# AnalogIO.net
KiCad netlist of a schematic drawn in Altium Designer
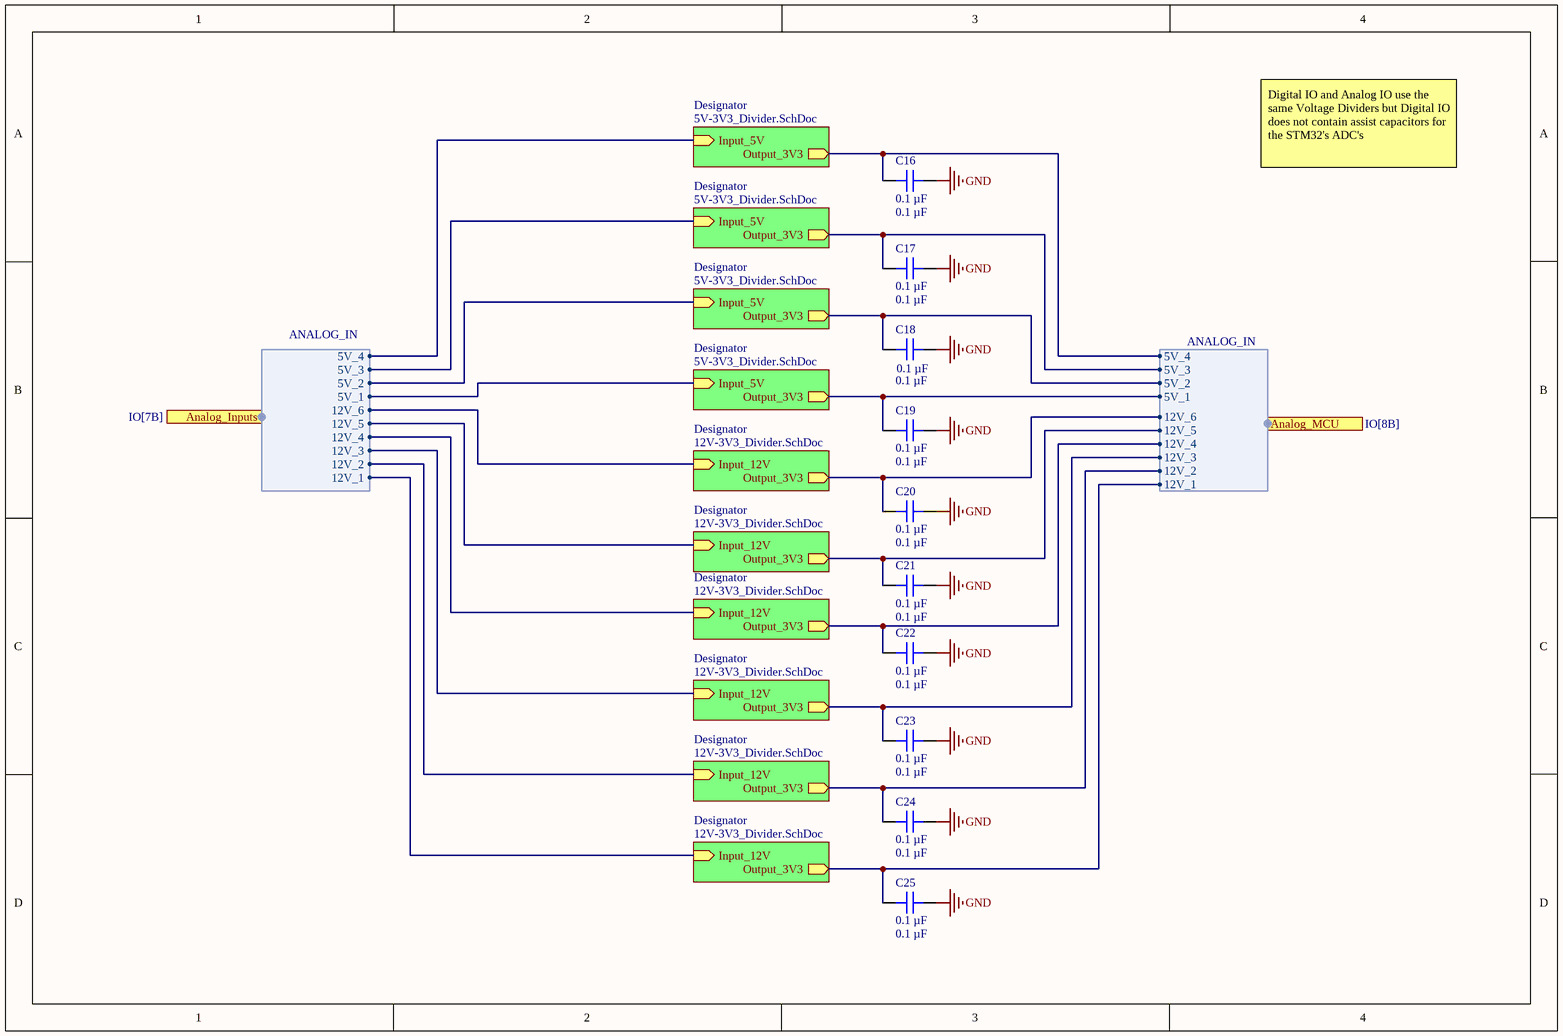
[diagram p0: AnalogIO.SchDoc]

(export (version "E")
  (design (tool "Eeschema 10.0.6"))
  (components
    (comp (ref "C16")
      (value "0.1 µF")
      (footprint "CAP 0603_1608")
      (description "CAP CER 0.1UF 16V X7R 0603")
      (fields (field (name "PART NUMBER") "CS0603KRX7R7BB104") (field (name "ALTIUM_VALUE") "0.1 µF"))
      (libsource (lib "altium_library") (part "Capacitor"))
    )
    (comp (ref "C17")
      (value "0.1 µF")
      (footprint "CAP 0603_1608")
      (description "CAP CER 0.1UF 16V X7R 0603")
      (fields (field (name "PART NUMBER") "CS0603KRX7R7BB104") (field (name "ALTIUM_VALUE") "0.1 µF"))
      (libsource (lib "altium_library") (part "Capacitor"))
    )
    (comp (ref "C18")
      (value "0.1 µF")
      (footprint "CAP 0603_1608")
      (description "CAP CER 0.1UF 16V X7R 0603")
      (fields (field (name "PART NUMBER") "CS0603KRX7R7BB104") (field (name "ALTIUM_VALUE") "0.1 µF"))
      (libsource (lib "altium_library") (part "Capacitor"))
    )
    (comp (ref "C19")
      (value "0.1 µF")
      (footprint "CAP 0603_1608")
      (description "CAP CER 0.1UF 16V X7R 0603")
      (fields (field (name "PART NUMBER") "CS0603KRX7R7BB104") (field (name "ALTIUM_VALUE") "0.1 µF"))
      (libsource (lib "altium_library") (part "Capacitor"))
    )
    (comp (ref "C20")
      (value "0.1 µF")
      (footprint "CAP 0603_1608")
      (description "CAP CER 0.1UF 16V X7R 0603")
      (fields (field (name "PART NUMBER") "CS0603KRX7R7BB104") (field (name "ALTIUM_VALUE") "0.1 µF"))
      (libsource (lib "altium_library") (part "Capacitor"))
    )
    (comp (ref "C21")
      (value "0.1 µF")
      (footprint "CAP 0603_1608")
      (description "CAP CER 0.1UF 16V X7R 0603")
      (fields (field (name "PART NUMBER") "CS0603KRX7R7BB104") (field (name "ALTIUM_VALUE") "0.1 µF"))
      (libsource (lib "altium_library") (part "Capacitor"))
    )
    (comp (ref "C22")
      (value "0.1 µF")
      (footprint "CAP 0603_1608")
      (description "CAP CER 0.1UF 16V X7R 0603")
      (fields (field (name "PART NUMBER") "CS0603KRX7R7BB104") (field (name "ALTIUM_VALUE") "0.1 µF"))
      (libsource (lib "altium_library") (part "Capacitor"))
    )
    (comp (ref "C23")
      (value "0.1 µF")
      (footprint "CAP 0603_1608")
      (description "CAP CER 0.1UF 16V X7R 0603")
      (fields (field (name "PART NUMBER") "CS0603KRX7R7BB104") (field (name "ALTIUM_VALUE") "0.1 µF"))
      (libsource (lib "altium_library") (part "Capacitor"))
    )
    (comp (ref "C24")
      (value "0.1 µF")
      (footprint "CAP 0603_1608")
      (description "CAP CER 0.1UF 16V X7R 0603")
      (fields (field (name "PART NUMBER") "CS0603KRX7R7BB104") (field (name "ALTIUM_VALUE") "0.1 µF"))
      (libsource (lib "altium_library") (part "Capacitor"))
    )
    (comp (ref "C25")
      (value "0.1 µF")
      (footprint "CAP 0603_1608")
      (description "CAP CER 0.1UF 16V X7R 0603")
      (fields (field (name "PART NUMBER") "CS0603KRX7R7BB104") (field (name "ALTIUM_VALUE") "0.1 µF"))
      (libsource (lib "altium_library") (part "Capacitor"))
    )
  )
  (nets
    (net (code "12") (name "/Output_3V3") (class "Default")
      (node (ref "C25") (pin "1") (pinfunction "1_1") (pintype "passive"))
    )
    (net (code "13") (name "/Output_3V3_1") (class "Default")
      (node (ref "C16") (pin "1") (pinfunction "1_1") (pintype "passive"))
    )
    (net (code "14") (name "/Output_3V3_2") (class "Default")
      (node (ref "C17") (pin "1") (pinfunction "1_1") (pintype "passive"))
    )
    (net (code "15") (name "/Output_3V3_3") (class "Default")
      (node (ref "C18") (pin "1") (pinfunction "1_1") (pintype "passive"))
    )
    (net (code "16") (name "/Output_3V3_4") (class "Default")
      (node (ref "C20") (pin "1") (pinfunction "1_1") (pintype "passive"))
    )
    (net (code "17") (name "/Output_3V3_5") (class "Default")
      (node (ref "C21") (pin "1") (pinfunction "1_1") (pintype "passive"))
    )
    (net (code "18") (name "/Output_3V3_6") (class "Default")
      (node (ref "C22") (pin "1") (pinfunction "1_1") (pintype "passive"))
    )
    (net (code "19") (name "/Output_3V3_7") (class "Default")
      (node (ref "C19") (pin "1") (pinfunction "1_1") (pintype "passive"))
    )
    (net (code "20") (name "/Output_3V3_8") (class "Default")
      (node (ref "C23") (pin "1") (pinfunction "1_1") (pintype "passive"))
    )
    (net (code "21") (name "/Output_3V3_9") (class "Default")
      (node (ref "C24") (pin "1") (pinfunction "1_1") (pintype "passive"))
    )
    (net (code "23") (name "GND") (class "Default")
      (node (ref "C16") (pin "2") (pinfunction "2_2") (pintype "passive"))
      (node (ref "C17") (pin "2") (pinfunction "2_2") (pintype "passive"))
      (node (ref "C18") (pin "2") (pinfunction "2_2") (pintype "passive"))
      (node (ref "C19") (pin "2") (pinfunction "2_2") (pintype "passive"))
      (node (ref "C20") (pin "2") (pinfunction "2_2") (pintype "passive"))
      (node (ref "C21") (pin "2") (pinfunction "2_2") (pintype "passive"))
      (node (ref "C22") (pin "2") (pinfunction "2_2") (pintype "passive"))
      (node (ref "C23") (pin "2") (pinfunction "2_2") (pintype "passive"))
      (node (ref "C24") (pin "2") (pinfunction "2_2") (pintype "passive"))
      (node (ref "C25") (pin "2") (pinfunction "2_2") (pintype "passive"))
    )
  )
)
